# DriveBayLCD.net
KiCad netlist of a schematic drawn in EAGLE
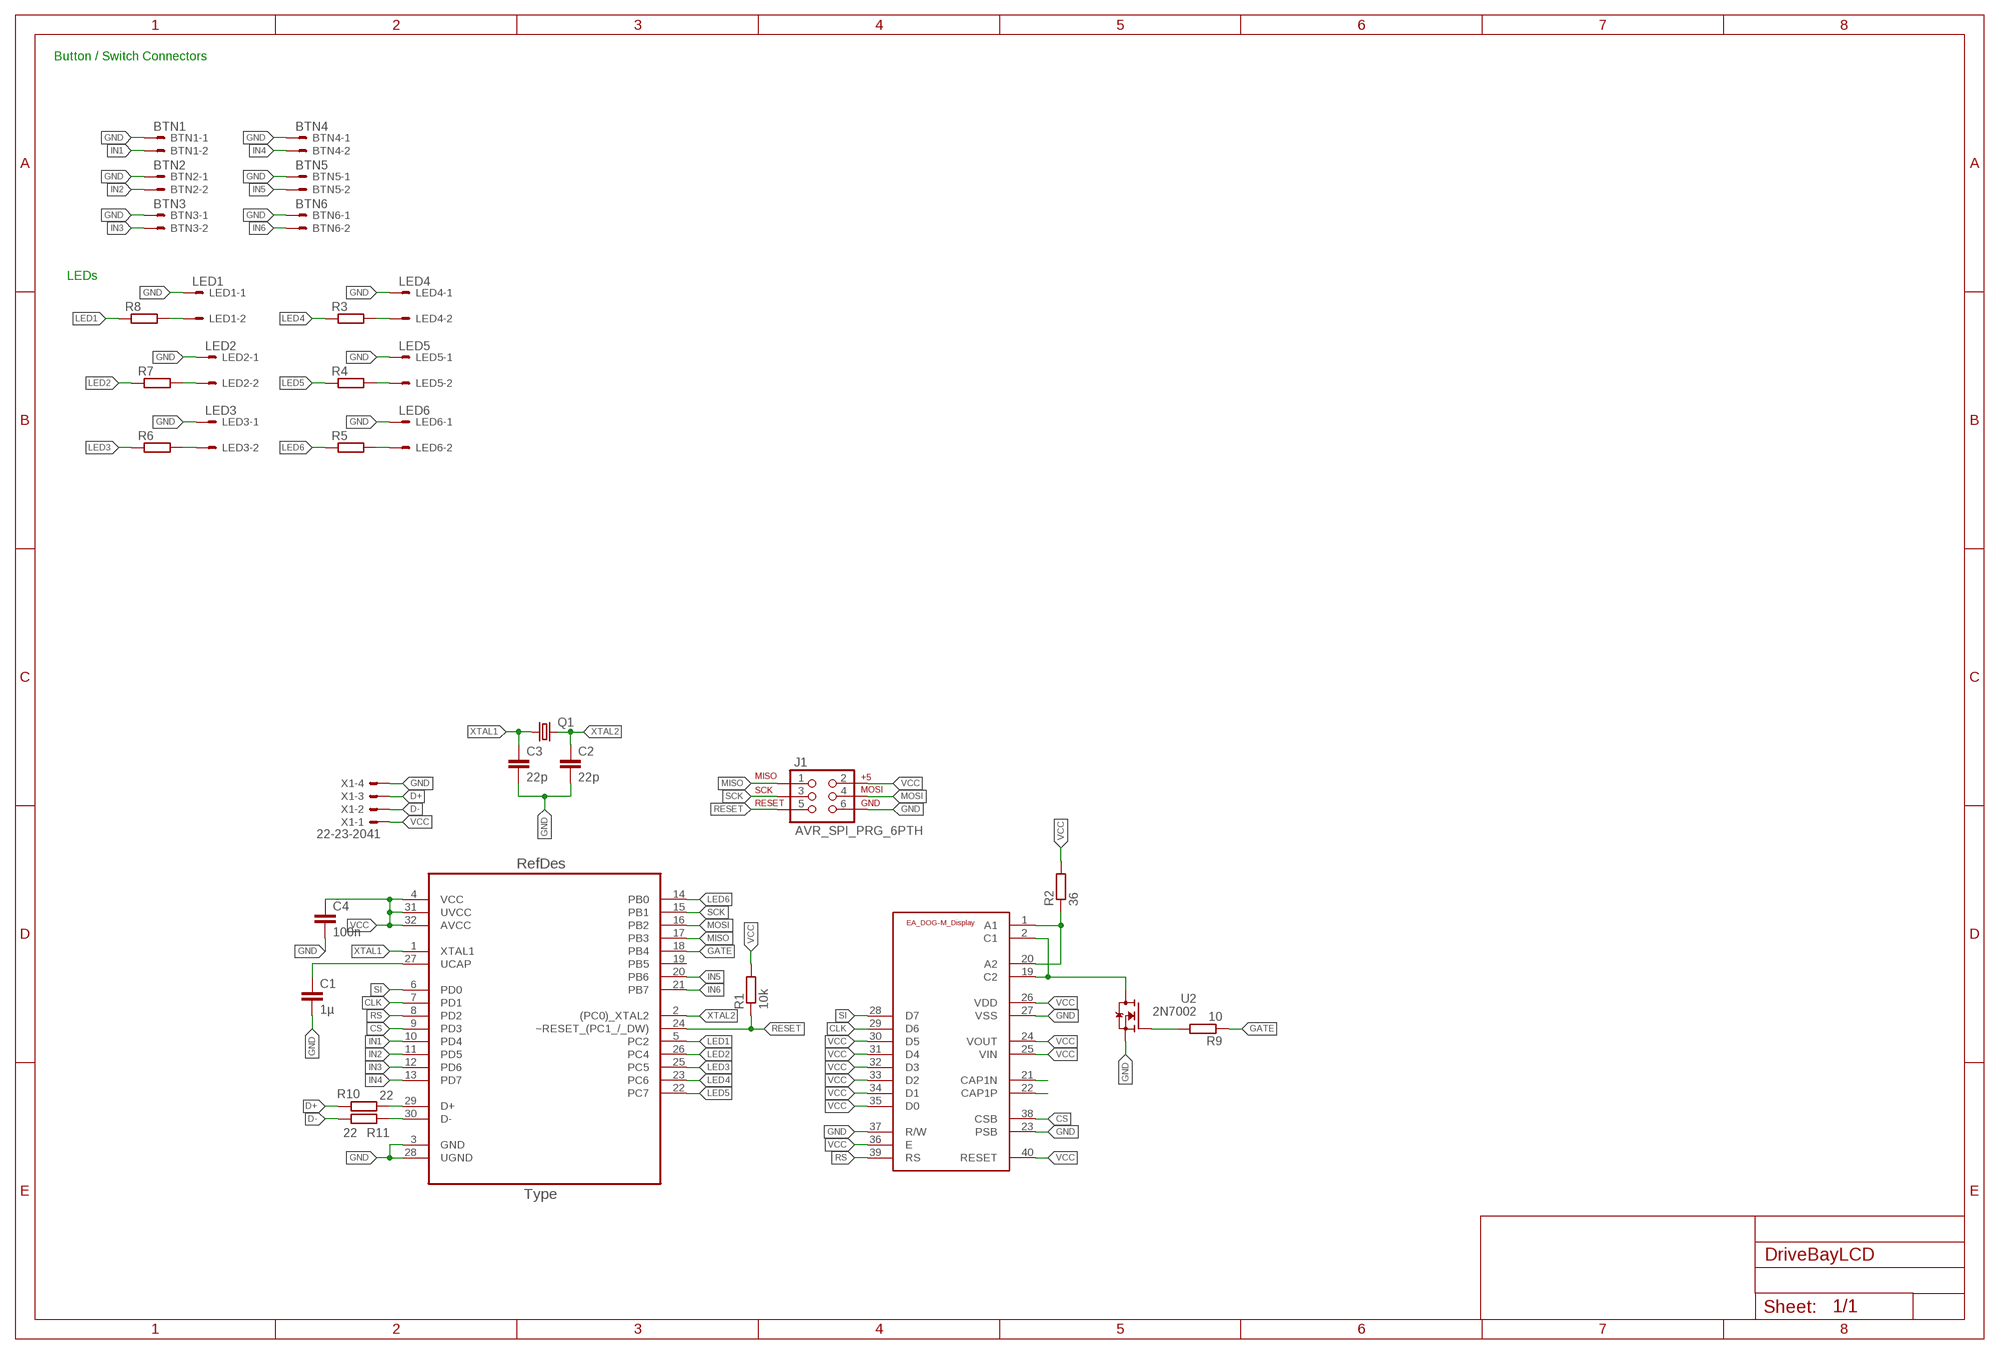
[diagram p0: schematic, sheet 1]

(export (version "E")
  (design (tool "Eeschema 10.0.6"))
  (components
    (comp (ref "BTN1")
      (value "BTN1")
      (footprint "eagle-import:22-23-2021")
      (fields (field (name "MF") "MOLEX") (field (name "MPN") "22-23-2021"))
      (libsource (lib "eagle-import") (part "22-23-2021"))
    )
    (comp (ref "BTN2")
      (value "BTN2")
      (footprint "eagle-import:22-23-2021")
      (fields (field (name "MF") "MOLEX") (field (name "MPN") "22-23-2021"))
      (libsource (lib "eagle-import") (part "22-23-2021"))
    )
    (comp (ref "BTN3")
      (value "BTN3")
      (footprint "eagle-import:22-23-2021")
      (fields (field (name "MF") "MOLEX") (field (name "MPN") "22-23-2021"))
      (libsource (lib "eagle-import") (part "22-23-2021"))
    )
    (comp (ref "BTN4")
      (value "BTN4")
      (footprint "eagle-import:22-23-2021")
      (fields (field (name "MF") "MOLEX") (field (name "MPN") "22-23-2021"))
      (libsource (lib "eagle-import") (part "22-23-2021"))
    )
    (comp (ref "BTN5")
      (value "BTN5")
      (footprint "eagle-import:22-23-2021")
      (fields (field (name "MF") "MOLEX") (field (name "MPN") "22-23-2021"))
      (libsource (lib "eagle-import") (part "22-23-2021"))
    )
    (comp (ref "BTN6")
      (value "BTN6")
      (footprint "eagle-import:22-23-2021")
      (fields (field (name "MF") "MOLEX") (field (name "MPN") "22-23-2021"))
      (libsource (lib "eagle-import") (part "22-23-2021"))
    )
    (comp (ref "C1")
      (value "1µ")
      (footprint "eagle-import:C0805")
      (libsource (lib "eagle-import") (part "C-EUC0805"))
    )
    (comp (ref "C2")
      (value "22p")
      (footprint "eagle-import:C0805")
      (libsource (lib "eagle-import") (part "C-EUC0805"))
    )
    (comp (ref "C3")
      (value "22p")
      (footprint "eagle-import:C0805")
      (libsource (lib "eagle-import") (part "C-EUC0805"))
    )
    (comp (ref "C4")
      (value "100n")
      (footprint "eagle-import:C0805")
      (libsource (lib "eagle-import") (part "C-EUC0805"))
    )
    (comp (ref "J1")
      (value "AVR_SPI_PRG_6PTH")
      (footprint "eagle-import:2X3")
      (libsource (lib "eagle-import") (part "AVR_SPI_PRG_6PTH"))
    )
    (comp (ref "LED1")
      (value "LED1")
      (footprint "eagle-import:22-23-2021")
      (fields (field (name "MF") "MOLEX") (field (name "MPN") "22-23-2021"))
      (libsource (lib "eagle-import") (part "22-23-2021"))
    )
    (comp (ref "LED2")
      (value "LED2")
      (footprint "eagle-import:22-23-2021")
      (fields (field (name "MF") "MOLEX") (field (name "MPN") "22-23-2021"))
      (libsource (lib "eagle-import") (part "22-23-2021"))
    )
    (comp (ref "LED3")
      (value "LED3")
      (footprint "eagle-import:22-23-2021")
      (fields (field (name "MF") "MOLEX") (field (name "MPN") "22-23-2021"))
      (libsource (lib "eagle-import") (part "22-23-2021"))
    )
    (comp (ref "LED4")
      (value "LED4")
      (footprint "eagle-import:22-23-2021")
      (fields (field (name "MF") "MOLEX") (field (name "MPN") "22-23-2021"))
      (libsource (lib "eagle-import") (part "22-23-2021"))
    )
    (comp (ref "LED5")
      (value "LED5")
      (footprint "eagle-import:22-23-2021")
      (fields (field (name "MF") "MOLEX") (field (name "MPN") "22-23-2021"))
      (libsource (lib "eagle-import") (part "22-23-2021"))
    )
    (comp (ref "LED6")
      (value "LED6")
      (footprint "eagle-import:22-23-2021")
      (fields (field (name "MF") "MOLEX") (field (name "MPN") "22-23-2021"))
      (libsource (lib "eagle-import") (part "22-23-2021"))
    )
    (comp (ref "Q1")
      (value "CRYSTALHC49S")
      (footprint "eagle-import:HC49_S")
      (libsource (lib "eagle-import") (part "CRYSTALHC49S"))
    )
    (comp (ref "R1")
      (value "10k")
      (footprint "eagle-import:R0805")
      (libsource (lib "eagle-import") (part "R-EU_R0805"))
    )
    (comp (ref "R2")
      (value "36")
      (footprint "eagle-import:R0805")
      (libsource (lib "eagle-import") (part "R-EU_R0805"))
    )
    (comp (ref "R3")
      (value "R-EU_R0805")
      (footprint "eagle-import:R0805")
      (libsource (lib "eagle-import") (part "R-EU_R0805"))
    )
    (comp (ref "R4")
      (value "R-EU_R0805")
      (footprint "eagle-import:R0805")
      (libsource (lib "eagle-import") (part "R-EU_R0805"))
    )
    (comp (ref "R5")
      (value "R-EU_R0805")
      (footprint "eagle-import:R0805")
      (libsource (lib "eagle-import") (part "R-EU_R0805"))
    )
    (comp (ref "R6")
      (value "R-EU_R0805")
      (footprint "eagle-import:R0805")
      (libsource (lib "eagle-import") (part "R-EU_R0805"))
    )
    (comp (ref "R7")
      (value "R-EU_R0805")
      (footprint "eagle-import:R0805")
      (libsource (lib "eagle-import") (part "R-EU_R0805"))
    )
    (comp (ref "R8")
      (value "R-EU_R0805")
      (footprint "eagle-import:R0805")
      (libsource (lib "eagle-import") (part "R-EU_R0805"))
    )
    (comp (ref "R9")
      (value "10")
      (footprint "eagle-import:R0805")
      (libsource (lib "eagle-import") (part "R-EU_R0805"))
    )
    (comp (ref "R10")
      (value "22")
      (footprint "eagle-import:R0805")
      (libsource (lib "eagle-import") (part "R-EU_R0805"))
    )
    (comp (ref "R11")
      (value "22")
      (footprint "eagle-import:R0805")
      (libsource (lib "eagle-import") (part "R-EU_R0805"))
    )
    (comp (ref "U$1")
      (value "EA_DOG-M_DISPLAY")
      (footprint "eagle-import:E_DOG-M_DISPLAY")
      (libsource (lib "eagle-import") (part "EA_DOG-M_DISPLAY"))
    )
    (comp (ref "U1")
      (value "ATMEGA32U2-AU")
      (footprint "eagle-import:QFP80P900X900X120-32N")
      (libsource (lib "eagle-import") (part "ATMEGA32U2-AU"))
    )
    (comp (ref "U2")
      (value "2N7002")
      (footprint "eagle-import:SOT23-3-ROTATED")
      (fields (field (name "MPN") "2N7002-7-F"))
      (libsource (lib "eagle-import") (part "2N7002"))
    )
    (comp (ref "X1")
      (value "22-23-2041")
      (footprint "eagle-import:22-23-2041")
      (fields (field (name "MF") "MOLEX"))
      (libsource (lib "eagle-import") (part "22-23-2041"))
    )
  )
  (nets
    (net (code "1") (name "CLK") (class "Default")
      (node (ref "U$1") (pin "29") (pinfunction "D6_29") (pintype "bidirectional"))
      (node (ref "U1") (pin "7") (pinfunction "PD1_7") (pintype "bidirectional"))
    )
    (net (code "2") (name "CS") (class "Default")
      (node (ref "U$1") (pin "38") (pinfunction "CSB_38") (pintype "bidirectional"))
      (node (ref "U1") (pin "9") (pinfunction "PD3_9") (pintype "bidirectional"))
    )
    (net (code "3") (name "D+") (class "Default")
      (node (ref "R10") (pin "2") (pinfunction "2_2") (pintype "passive"))
      (node (ref "X1") (pin "3") (pinfunction "S_3") (pintype "passive"))
    )
    (net (code "4") (name "D-") (class "Default")
      (node (ref "R11") (pin "2") (pinfunction "2_2") (pintype "passive"))
      (node (ref "X1") (pin "2") (pinfunction "S_2") (pintype "passive"))
    )
    (net (code "5") (name "GATE") (class "Default")
      (node (ref "R9") (pin "1") (pinfunction "1_1") (pintype "passive"))
      (node (ref "U1") (pin "18") (pinfunction "PB4_18") (pintype "bidirectional"))
    )
    (net (code "6") (name "GND") (class "Default")
      (node (ref "BTN1") (pin "1") (pinfunction "S_1") (pintype "passive"))
      (node (ref "BTN2") (pin "1") (pinfunction "S_1") (pintype "passive"))
      (node (ref "BTN3") (pin "1") (pinfunction "S_1") (pintype "passive"))
      (node (ref "BTN4") (pin "1") (pinfunction "S_1") (pintype "passive"))
      (node (ref "BTN5") (pin "1") (pinfunction "S_1") (pintype "passive"))
      (node (ref "BTN6") (pin "1") (pinfunction "S_1") (pintype "passive"))
      (node (ref "C1") (pin "2") (pinfunction "2_2") (pintype "passive"))
      (node (ref "C2") (pin "2") (pinfunction "2_2") (pintype "passive"))
      (node (ref "C3") (pin "2") (pinfunction "2_2") (pintype "passive"))
      (node (ref "C4") (pin "2") (pinfunction "2_2") (pintype "passive"))
      (node (ref "J1") (pin "6") (pinfunction "6_6") (pintype "passive"))
      (node (ref "LED1") (pin "1") (pinfunction "S_1") (pintype "passive"))
      (node (ref "LED2") (pin "1") (pinfunction "S_1") (pintype "passive"))
      (node (ref "LED3") (pin "1") (pinfunction "S_1") (pintype "passive"))
      (node (ref "LED4") (pin "1") (pinfunction "S_1") (pintype "passive"))
      (node (ref "LED5") (pin "1") (pinfunction "S_1") (pintype "passive"))
      (node (ref "LED6") (pin "1") (pinfunction "S_1") (pintype "passive"))
      (node (ref "U$1") (pin "23") (pinfunction "PSB_23") (pintype "bidirectional"))
      (node (ref "U$1") (pin "27") (pinfunction "VSS_27") (pintype "power_in"))
      (node (ref "U$1") (pin "37") (pinfunction "R/W_37") (pintype "bidirectional"))
      (node (ref "U1") (pin "28") (pinfunction "UGND_28") (pintype "passive"))
      (node (ref "U1") (pin "3") (pinfunction "GND_3") (pintype "passive"))
      (node (ref "U2") (pin "2") (pinfunction "S_2") (pintype "passive"))
      (node (ref "X1") (pin "4") (pinfunction "S_4") (pintype "passive"))
    )
    (net (code "7") (name "IN1") (class "Default")
      (node (ref "BTN1") (pin "2") (pinfunction "S_2") (pintype "passive"))
      (node (ref "U1") (pin "10") (pinfunction "PD4_10") (pintype "bidirectional"))
    )
    (net (code "8") (name "IN2") (class "Default")
      (node (ref "BTN2") (pin "2") (pinfunction "S_2") (pintype "passive"))
      (node (ref "U1") (pin "11") (pinfunction "PD5_11") (pintype "bidirectional"))
    )
    (net (code "9") (name "IN3") (class "Default")
      (node (ref "BTN3") (pin "2") (pinfunction "S_2") (pintype "passive"))
      (node (ref "U1") (pin "12") (pinfunction "PD6_12") (pintype "bidirectional"))
    )
    (net (code "10") (name "IN4") (class "Default")
      (node (ref "BTN4") (pin "2") (pinfunction "S_2") (pintype "passive"))
      (node (ref "U1") (pin "13") (pinfunction "PD7_13") (pintype "bidirectional"))
    )
    (net (code "11") (name "IN5") (class "Default")
      (node (ref "BTN5") (pin "2") (pinfunction "S_2") (pintype "passive"))
      (node (ref "U1") (pin "20") (pinfunction "PB6_20") (pintype "bidirectional"))
    )
    (net (code "12") (name "IN6") (class "Default")
      (node (ref "BTN6") (pin "2") (pinfunction "S_2") (pintype "passive"))
      (node (ref "U1") (pin "21") (pinfunction "PB7_21") (pintype "bidirectional"))
    )
    (net (code "13") (name "LED1") (class "Default")
      (node (ref "R8") (pin "1") (pinfunction "1_1") (pintype "passive"))
      (node (ref "U1") (pin "5") (pinfunction "PC2_5") (pintype "bidirectional"))
    )
    (net (code "14") (name "LED2") (class "Default")
      (node (ref "R7") (pin "1") (pinfunction "1_1") (pintype "passive"))
      (node (ref "U1") (pin "26") (pinfunction "PC4_26") (pintype "bidirectional"))
    )
    (net (code "15") (name "LED3") (class "Default")
      (node (ref "R6") (pin "1") (pinfunction "1_1") (pintype "passive"))
      (node (ref "U1") (pin "25") (pinfunction "PC5_25") (pintype "bidirectional"))
    )
    (net (code "16") (name "LED4") (class "Default")
      (node (ref "R3") (pin "1") (pinfunction "1_1") (pintype "passive"))
      (node (ref "U1") (pin "23") (pinfunction "PC6_23") (pintype "bidirectional"))
    )
    (net (code "17") (name "LED5") (class "Default")
      (node (ref "R4") (pin "1") (pinfunction "1_1") (pintype "passive"))
      (node (ref "U1") (pin "22") (pinfunction "PC7_22") (pintype "bidirectional"))
    )
    (net (code "18") (name "LED6") (class "Default")
      (node (ref "R5") (pin "1") (pinfunction "1_1") (pintype "passive"))
      (node (ref "U1") (pin "14") (pinfunction "PB0_14") (pintype "bidirectional"))
    )
    (net (code "19") (name "MISO") (class "Default")
      (node (ref "J1") (pin "1") (pinfunction "1_1") (pintype "passive"))
      (node (ref "U1") (pin "17") (pinfunction "PB3_17") (pintype "bidirectional"))
    )
    (net (code "20") (name "MOSI") (class "Default")
      (node (ref "J1") (pin "4") (pinfunction "4_4") (pintype "passive"))
      (node (ref "U1") (pin "16") (pinfunction "PB2_16") (pintype "bidirectional"))
    )
    (net (code "21") (name "Net-(LED1B-S)") (class "Default")
      (node (ref "LED1") (pin "2") (pinfunction "S_2") (pintype "passive"))
      (node (ref "R8") (pin "2") (pinfunction "2_2") (pintype "passive"))
    )
    (net (code "22") (name "Net-(LED2B-S)") (class "Default")
      (node (ref "LED2") (pin "2") (pinfunction "S_2") (pintype "passive"))
      (node (ref "R7") (pin "2") (pinfunction "2_2") (pintype "passive"))
    )
    (net (code "23") (name "Net-(LED3B-S)") (class "Default")
      (node (ref "LED3") (pin "2") (pinfunction "S_2") (pintype "passive"))
      (node (ref "R6") (pin "2") (pinfunction "2_2") (pintype "passive"))
    )
    (net (code "24") (name "Net-(LED4B-S)") (class "Default")
      (node (ref "LED4") (pin "2") (pinfunction "S_2") (pintype "passive"))
      (node (ref "R3") (pin "2") (pinfunction "2_2") (pintype "passive"))
    )
    (net (code "25") (name "Net-(LED5B-S)") (class "Default")
      (node (ref "LED5") (pin "2") (pinfunction "S_2") (pintype "passive"))
      (node (ref "R4") (pin "2") (pinfunction "2_2") (pintype "passive"))
    )
    (net (code "26") (name "Net-(LED6B-S)") (class "Default")
      (node (ref "LED6") (pin "2") (pinfunction "S_2") (pintype "passive"))
      (node (ref "R5") (pin "2") (pinfunction "2_2") (pintype "passive"))
    )
    (net (code "27") (name "Net-(U$1-A1)") (class "Default")
      (node (ref "R2") (pin "1") (pinfunction "1_1") (pintype "passive"))
      (node (ref "U$1") (pin "1") (pinfunction "A1_1") (pintype "bidirectional"))
      (node (ref "U$1") (pin "20") (pinfunction "A2_20") (pintype "bidirectional"))
    )
    (net (code "28") (name "Net-(U$1-C1)") (class "Default")
      (node (ref "U$1") (pin "19") (pinfunction "C2_19") (pintype "bidirectional"))
      (node (ref "U$1") (pin "2") (pinfunction "C1_2") (pintype "bidirectional"))
      (node (ref "U2") (pin "3") (pinfunction "D_3") (pintype "passive"))
    )
    (net (code "29") (name "Net-(U1-D+)") (class "Default")
      (node (ref "R10") (pin "1") (pinfunction "1_1") (pintype "passive"))
      (node (ref "U1") (pin "29") (pinfunction "D+_29") (pintype "bidirectional"))
    )
    (net (code "30") (name "Net-(U1-D-)") (class "Default")
      (node (ref "R11") (pin "1") (pinfunction "1_1") (pintype "passive"))
      (node (ref "U1") (pin "30") (pinfunction "D-_30") (pintype "bidirectional"))
    )
    (net (code "31") (name "Net-(U1-UCAP)") (class "Default")
      (node (ref "C1") (pin "1") (pinfunction "1_1") (pintype "passive"))
      (node (ref "U1") (pin "27") (pinfunction "UCAP_27") (pintype "power_in"))
    )
    (net (code "32") (name "Net-(U2-G)") (class "Default")
      (node (ref "R9") (pin "2") (pinfunction "2_2") (pintype "passive"))
      (node (ref "U2") (pin "1") (pinfunction "G_1") (pintype "passive"))
    )
    (net (code "33") (name "RESET") (class "Default")
      (node (ref "J1") (pin "5") (pinfunction "5_5") (pintype "passive"))
      (node (ref "R1") (pin "1") (pinfunction "1_1") (pintype "passive"))
      (node (ref "U1") (pin "24") (pinfunction "~{RESET_(PC1_/_DW})_24") (pintype "bidirectional"))
    )
    (net (code "34") (name "RS") (class "Default")
      (node (ref "U$1") (pin "39") (pinfunction "RS_39") (pintype "bidirectional"))
      (node (ref "U1") (pin "8") (pinfunction "PD2_8") (pintype "bidirectional"))
    )
    (net (code "35") (name "SCK") (class "Default")
      (node (ref "J1") (pin "3") (pinfunction "3_3") (pintype "passive"))
      (node (ref "U1") (pin "15") (pinfunction "PB1_15") (pintype "bidirectional"))
    )
    (net (code "36") (name "SI") (class "Default")
      (node (ref "U$1") (pin "28") (pinfunction "D7_28") (pintype "bidirectional"))
      (node (ref "U1") (pin "6") (pinfunction "PD0_6") (pintype "bidirectional"))
    )
    (net (code "37") (name "VCC") (class "Default")
      (node (ref "C4") (pin "1") (pinfunction "1_1") (pintype "passive"))
      (node (ref "J1") (pin "2") (pinfunction "2_2") (pintype "passive"))
      (node (ref "R1") (pin "2") (pinfunction "2_2") (pintype "passive"))
      (node (ref "R2") (pin "2") (pinfunction "2_2") (pintype "passive"))
      (node (ref "U$1") (pin "24") (pinfunction "VOUT_24") (pintype "bidirectional"))
      (node (ref "U$1") (pin "25") (pinfunction "VIN_25") (pintype "bidirectional"))
      (node (ref "U$1") (pin "26") (pinfunction "VDD_26") (pintype "power_in"))
      (node (ref "U$1") (pin "30") (pinfunction "D5_30") (pintype "bidirectional"))
      (node (ref "U$1") (pin "31") (pinfunction "D4_31") (pintype "bidirectional"))
      (node (ref "U$1") (pin "32") (pinfunction "D3_32") (pintype "bidirectional"))
      (node (ref "U$1") (pin "33") (pinfunction "D2_33") (pintype "bidirectional"))
      (node (ref "U$1") (pin "34") (pinfunction "D1_34") (pintype "bidirectional"))
      (node (ref "U$1") (pin "35") (pinfunction "D0_35") (pintype "bidirectional"))
      (node (ref "U$1") (pin "36") (pinfunction "E_36") (pintype "bidirectional"))
      (node (ref "U$1") (pin "40") (pinfunction "RESET_40") (pintype "bidirectional"))
      (node (ref "U1") (pin "31") (pinfunction "UVCC_31") (pintype "power_in"))
      (node (ref "U1") (pin "32") (pinfunction "AVCC_32") (pintype "power_in"))
      (node (ref "U1") (pin "4") (pinfunction "VCC_4") (pintype "power_in"))
      (node (ref "X1") (pin "1") (pinfunction "S_1") (pintype "passive"))
    )
    (net (code "38") (name "XTAL1") (class "Default")
      (node (ref "C3") (pin "1") (pinfunction "1_1") (pintype "passive"))
      (node (ref "Q1") (pin "1") (pinfunction "1_1") (pintype "passive"))
      (node (ref "U1") (pin "1") (pinfunction "XTAL1_1") (pintype "input"))
    )
    (net (code "39") (name "XTAL2") (class "Default")
      (node (ref "C2") (pin "1") (pinfunction "1_1") (pintype "passive"))
      (node (ref "Q1") (pin "2") (pinfunction "2_2") (pintype "passive"))
      (node (ref "U1") (pin "2") (pinfunction "(PC0)_XTAL2_2") (pintype "bidirectional"))
    )
    (net (code "40") (name "unconnected-(U$1-CAP1N-Pad21)") (class "Default")
      (node (ref "U$1") (pin "21") (pinfunction "CAP1N_21") (pintype "bidirectional"))
    )
    (net (code "41") (name "unconnected-(U$1-CAP1P-Pad22)") (class "Default")
      (node (ref "U$1") (pin "22") (pinfunction "CAP1P_22") (pintype "bidirectional"))
    )
    (net (code "42") (name "unconnected-(U1-PB5-Pad19)") (class "Default")
      (node (ref "U1") (pin "19") (pinfunction "PB5_19") (pintype "bidirectional"))
    )
  )
)
